# clock.net
KiCad netlist of a schematic drawn in EAGLE
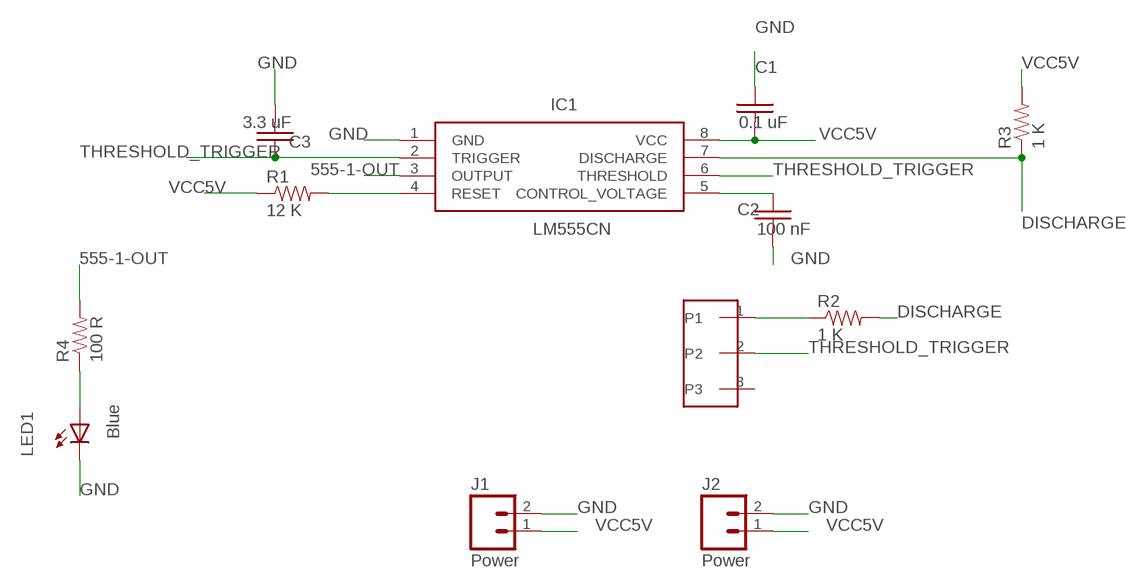
[diagram p0: schematic, sheet 1]
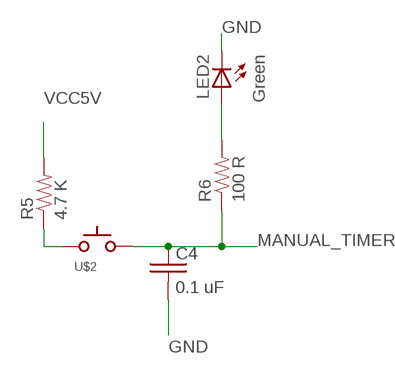
[diagram p1: schematic, sheet 2]
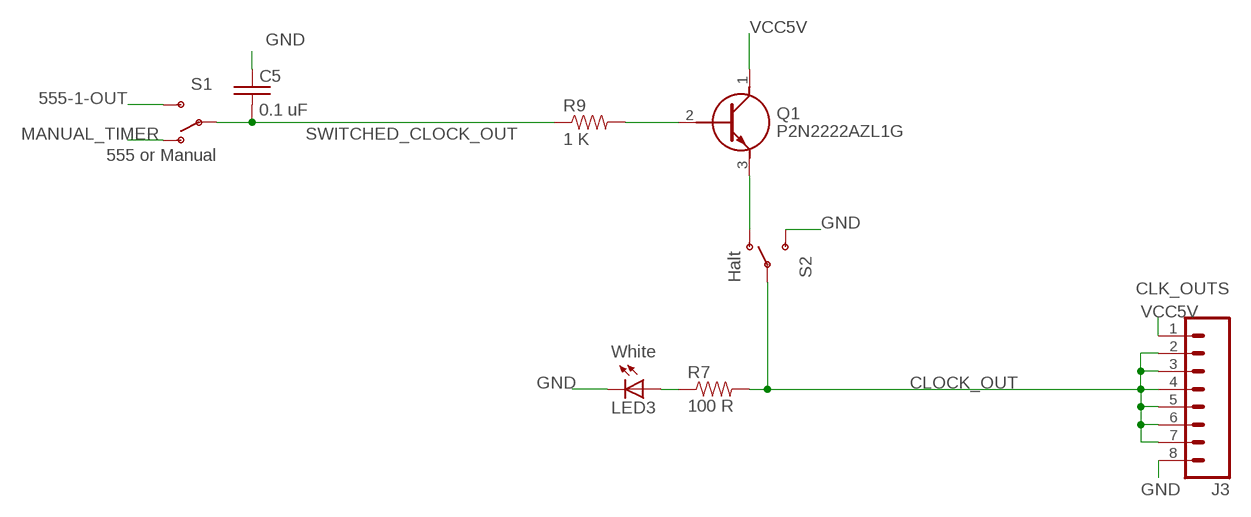
[diagram p2: schematic, sheet 3]
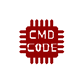
[diagram p3: schematic, sheet 4]

(export (version "E")
  (design (tool "Eeschema 10.0.6"))
  (components
    (comp (ref "C5")
      (value "0.1 uF")
      (footprint "eagle-import:C0805")
      (libsource (lib "eagle-import") (part "C-USC0805"))
    )
    (comp (ref "J3")
      (value "CLK_OUTS")
      (footprint "eagle-import:1X08")
      (libsource (lib "eagle-import") (part "M08SILK_FEMALE_PTH"))
    )
    (comp (ref "LED3")
      (value "White")
      (footprint "eagle-import:LED3MM-NS")
      (libsource (lib "eagle-import") (part "LED-3MM-NO_SILK"))
    )
    (comp (ref "Q1")
      (value "P2N2222AZL1G")
      (footprint "eagle-import:2N6027")
      (fields (field (name "MOUSER_PART_NUMBER") "863-P2N2222AZL1G"))
      (libsource (lib "eagle-import") (part "P2N2222AZL1G"))
    )
    (comp (ref "R7")
      (value "100 R")
      (footprint "eagle-import:0805")
      (libsource (lib "eagle-import") (part "RESISTOR0805-RES"))
    )
    (comp (ref "R9")
      (value "1 K")
      (footprint "eagle-import:0805")
      (libsource (lib "eagle-import") (part "RESISTOR0805-RES"))
    )
    (comp (ref "S1")
      (value "555 or Manual")
      (footprint "eagle-import:SWITCH-SPDT_KIT")
      (libsource (lib "eagle-import") (part "SWITCH-SPSTKIT"))
    )
    (comp (ref "S2")
      (value "Halt")
      (footprint "eagle-import:SWITCH-SPDT_KIT")
      (libsource (lib "eagle-import") (part "SWITCH-SPSTKIT"))
    )
    (comp (ref "C4")
      (value "0.1 uF")
      (footprint "eagle-import:C0805")
      (libsource (lib "eagle-import") (part "C-USC0805"))
    )
    (comp (ref "LED2")
      (value "Green")
      (footprint "eagle-import:LED3MM-NS")
      (libsource (lib "eagle-import") (part "LED-3MM-NO_SILK"))
    )
    (comp (ref "R5")
      (value "4.7 K")
      (footprint "eagle-import:0805")
      (libsource (lib "eagle-import") (part "RESISTOR0805-RES"))
    )
    (comp (ref "R6")
      (value "100 R")
      (footprint "eagle-import:0805")
      (libsource (lib "eagle-import") (part "RESISTOR0805-RES"))
    )
    (comp (ref "U$2")
      (value "SWITCH_TACTILETACTILE_PIN")
      (footprint "eagle-import:TACTILE-PTH")
      (libsource (lib "eagle-import") (part "SWITCH_TACTILETACTILE_PIN"))
    )
    (comp (ref "U$3")
      (value "CMD_C0DE_LOGOCMD_CODE_LOGO_TOP_COPPER")
      (footprint "eagle-import:CMD_C0DE_LOGO_TOP_COPPER")
      (libsource (lib "eagle-import") (part "CMD_C0DE_LOGOCMD_CODE_LOGO_TOP_COPPER"))
    )
    (comp (ref "C1")
      (value "0.1 uF")
      (footprint "eagle-import:C0805")
      (libsource (lib "eagle-import") (part "C-USC0805"))
    )
    (comp (ref "C2")
      (value "100 nF")
      (footprint "eagle-import:C0805K")
      (libsource (lib "eagle-import") (part "C-USC0805K"))
    )
    (comp (ref "C3")
      (value "3.3 uF")
      (footprint "eagle-import:C0805")
      (libsource (lib "eagle-import") (part "C-USC0805"))
    )
    (comp (ref "IC1")
      (value "LM555CN")
      (footprint "eagle-import:DIP762W53P254L980H533Q8N")
      (fields (field (name "MOUSER_PART_NUMBER") "512-LM555CN") (field (name "RS_PART_NUMBER") "1698718"))
      (libsource (lib "eagle-import") (part "LM555CN"))
    )
    (comp (ref "J1")
      (value "Power")
      (footprint "eagle-import:1X02")
      (libsource (lib "eagle-import") (part "M02PTH"))
    )
    (comp (ref "J2")
      (value "Power")
      (footprint "eagle-import:1X02")
      (libsource (lib "eagle-import") (part "M02PTH"))
    )
    (comp (ref "LED1")
      (value "Blue")
      (footprint "eagle-import:LED3MM-NS")
      (libsource (lib "eagle-import") (part "LED-3MM-NO_SILK"))
    )
    (comp (ref "R1")
      (value "12 K")
      (footprint "eagle-import:0805")
      (libsource (lib "eagle-import") (part "RESISTOR0805-RES"))
    )
    (comp (ref "R2")
      (value "1 K")
      (footprint "eagle-import:0805")
      (libsource (lib "eagle-import") (part "RESISTOR0805-RES"))
    )
    (comp (ref "R3")
      (value "1 K")
      (footprint "eagle-import:0805")
      (libsource (lib "eagle-import") (part "RESISTOR0805-RES"))
    )
    (comp (ref "R4")
      (value "100 R")
      (footprint "eagle-import:0805")
      (libsource (lib "eagle-import") (part "RESISTOR0805-RES"))
    )
    (comp (ref "U$1")
      (value "SQUARE-TRIMPOT-POTENTIOMETER")
      (footprint "eagle-import:3_8-SQUARE-TRIMPOT")
      (libsource (lib "eagle-import") (part "SQUARE-TRIMPOT-POTENTIOMETER"))
    )
  )
  (nets
    (net (code "1") (name "555-1-OUT") (class "Default")
      (node (ref "IC1") (pin "3") (pinfunction "OUTPUT_3") (pintype "bidirectional"))
      (node (ref "R4") (pin "2") (pinfunction "2_2") (pintype "passive"))
      (node (ref "S1") (pin "3") (pinfunction "S_3") (pintype "passive"))
    )
    (net (code "2") (name "CLOCK_OUT") (class "Default")
      (node (ref "J3") (pin "2") (pinfunction "2_2") (pintype "passive"))
      (node (ref "J3") (pin "3") (pinfunction "3_3") (pintype "passive"))
      (node (ref "J3") (pin "4") (pinfunction "4_4") (pintype "passive"))
      (node (ref "J3") (pin "5") (pinfunction "5_5") (pintype "passive"))
      (node (ref "J3") (pin "6") (pinfunction "6_6") (pintype "passive"))
      (node (ref "J3") (pin "7") (pinfunction "7_7") (pintype "passive"))
      (node (ref "R7") (pin "2") (pinfunction "2_2") (pintype "passive"))
      (node (ref "S2") (pin "2") (pinfunction "P_2") (pintype "passive"))
    )
    (net (code "3") (name "DISCHARGE") (class "Default")
      (node (ref "IC1") (pin "7") (pinfunction "DISCHARGE_7") (pintype "bidirectional"))
      (node (ref "R2") (pin "2") (pinfunction "2_2") (pintype "passive"))
      (node (ref "R3") (pin "1") (pinfunction "1_1") (pintype "passive"))
    )
    (net (code "4") (name "GND") (class "Default")
      (node (ref "C1") (pin "1") (pinfunction "1_1") (pintype "passive"))
      (node (ref "C2") (pin "2") (pinfunction "2_2") (pintype "passive"))
      (node (ref "C3") (pin "2") (pinfunction "2_2") (pintype "passive"))
      (node (ref "C4") (pin "2") (pinfunction "2_2") (pintype "passive"))
      (node (ref "C5") (pin "1") (pinfunction "1_1") (pintype "passive"))
      (node (ref "IC1") (pin "1") (pinfunction "GND_1") (pintype "bidirectional"))
      (node (ref "J1") (pin "2") (pinfunction "2_2") (pintype "passive"))
      (node (ref "J2") (pin "2") (pinfunction "2_2") (pintype "passive"))
      (node (ref "J3") (pin "8") (pinfunction "8_8") (pintype "passive"))
      (node (ref "LED1") (pin "K") (pinfunction "C_K") (pintype "output"))
      (node (ref "LED2") (pin "K") (pinfunction "C_K") (pintype "output"))
      (node (ref "LED3") (pin "K") (pinfunction "C_K") (pintype "output"))
      (node (ref "S2") (pin "3") (pinfunction "S_3") (pintype "passive"))
    )
    (net (code "5") (name "MANUAL_TIMER") (class "Default")
      (node (ref "C4") (pin "1") (pinfunction "1_1") (pintype "passive"))
      (node (ref "R6") (pin "1") (pinfunction "1_1") (pintype "passive"))
      (node (ref "S1") (pin "1") (pinfunction "O_1") (pintype "passive"))
      (node (ref "U$2") (pin "1") (pinfunction "A_1") (pintype "passive"))
      (node (ref "U$2") (pin "2") (pinfunction "A_2") (pintype "passive"))
    )
    (net (code "6") (name "Net-(IC1-CONTROL_VOLTAGE)") (class "Default")
      (node (ref "C2") (pin "1") (pinfunction "1_1") (pintype "passive"))
      (node (ref "IC1") (pin "5") (pinfunction "CONTROL_VOLTAGE_5") (pintype "bidirectional"))
    )
    (net (code "7") (name "Net-(IC1-RESET)") (class "Default")
      (node (ref "IC1") (pin "4") (pinfunction "RESET_4") (pintype "bidirectional"))
      (node (ref "R1") (pin "2") (pinfunction "2_2") (pintype "passive"))
    )
    (net (code "8") (name "Net-(LED1-PadA)") (class "Default")
      (node (ref "LED1") (pin "A") (pinfunction "A_A") (pintype "input"))
      (node (ref "R4") (pin "1") (pinfunction "1_1") (pintype "passive"))
    )
    (net (code "9") (name "Net-(LED2-PadA)") (class "Default")
      (node (ref "LED2") (pin "A") (pinfunction "A_A") (pintype "input"))
      (node (ref "R6") (pin "2") (pinfunction "2_2") (pintype "passive"))
    )
    (net (code "10") (name "Net-(LED3-PadA)") (class "Default")
      (node (ref "LED3") (pin "A") (pinfunction "A_A") (pintype "input"))
      (node (ref "R7") (pin "1") (pinfunction "1_1") (pintype "passive"))
    )
    (net (code "11") (name "Net-(Q1-B)") (class "Default")
      (node (ref "Q1") (pin "2") (pinfunction "B_2") (pintype "bidirectional"))
      (node (ref "R9") (pin "2") (pinfunction "2_2") (pintype "passive"))
    )
    (net (code "12") (name "Net-(Q1-E)") (class "Default")
      (node (ref "Q1") (pin "3") (pinfunction "E_3") (pintype "bidirectional"))
      (node (ref "S2") (pin "1") (pinfunction "O_1") (pintype "passive"))
    )
    (net (code "13") (name "Net-(R5-Pad1)") (class "Default")
      (node (ref "R5") (pin "1") (pinfunction "1_1") (pintype "passive"))
      (node (ref "U$2") (pin "3") (pinfunction "C_3") (pintype "passive"))
      (node (ref "U$2") (pin "4") (pinfunction "C_4") (pintype "passive"))
    )
    (net (code "14") (name "Net-(U$1-P1)") (class "Default")
      (node (ref "R2") (pin "1") (pinfunction "1_1") (pintype "passive"))
      (node (ref "U$1") (pin "1") (pinfunction "P1_1") (pintype "bidirectional"))
    )
    (net (code "15") (name "SWITCHED_CLOCK_OUT") (class "Default")
      (node (ref "C5") (pin "2") (pinfunction "2_2") (pintype "passive"))
      (node (ref "R9") (pin "1") (pinfunction "1_1") (pintype "passive"))
      (node (ref "S1") (pin "2") (pinfunction "P_2") (pintype "passive"))
    )
    (net (code "16") (name "THRESHOLD_TRIGGER") (class "Default")
      (node (ref "C3") (pin "1") (pinfunction "1_1") (pintype "passive"))
      (node (ref "IC1") (pin "2") (pinfunction "TRIGGER_2") (pintype "bidirectional"))
      (node (ref "IC1") (pin "6") (pinfunction "THRESHOLD_6") (pintype "bidirectional"))
      (node (ref "U$1") (pin "2") (pinfunction "P2_2") (pintype "bidirectional"))
    )
    (net (code "17") (name "VCC5V") (class "Default")
      (node (ref "C1") (pin "2") (pinfunction "2_2") (pintype "passive"))
      (node (ref "IC1") (pin "8") (pinfunction "VCC_8") (pintype "bidirectional"))
      (node (ref "J1") (pin "1") (pinfunction "1_1") (pintype "passive"))
      (node (ref "J2") (pin "1") (pinfunction "1_1") (pintype "passive"))
      (node (ref "J3") (pin "1") (pinfunction "1_1") (pintype "passive"))
      (node (ref "Q1") (pin "1") (pinfunction "C_1") (pintype "bidirectional"))
      (node (ref "R1") (pin "1") (pinfunction "1_1") (pintype "passive"))
      (node (ref "R3") (pin "2") (pinfunction "2_2") (pintype "passive"))
      (node (ref "R5") (pin "2") (pinfunction "2_2") (pintype "passive"))
    )
    (net (code "18") (name "unconnected-(U$1-P3-Pad3)") (class "Default")
      (node (ref "U$1") (pin "3") (pinfunction "P3_3") (pintype "bidirectional"))
    )
  )
)
